# Fuel_Gauge.net
KiCad netlist of a schematic drawn in Altium Designer
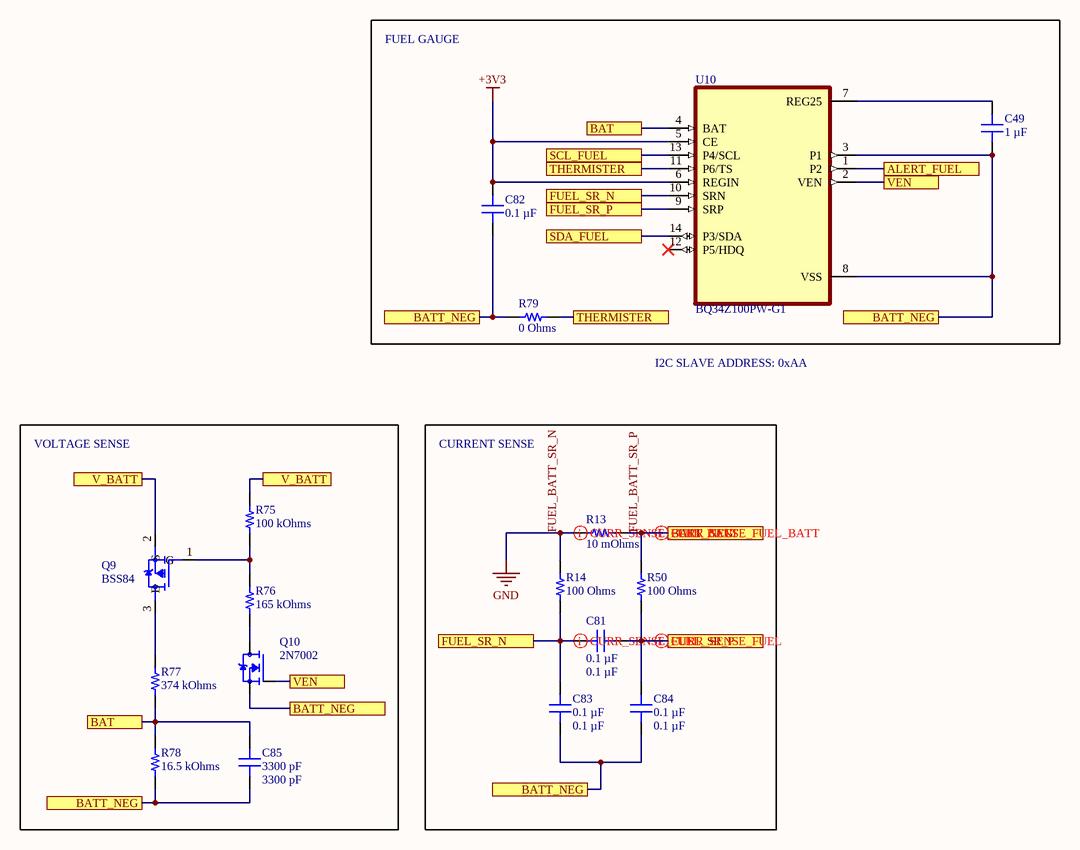
[diagram p0: Fuel_Gauge.SchDoc]

(export (version "E")
  (design (tool "Eeschema 10.0.6"))
  (components
    (comp (ref "C49")
      (value "1 µF")
      (footprint "CAP 0402_1005")
      (description "CAP CER 1UF 10V X5R 0402")
      (fields (field (name "PART NUMBER") "LMK105BJ105KPLF") (field (name "MANUFACTURER") "Taiyo Yuden"))
      (libsource (lib "Celestial Altium Library - altium_library") (part "Capacitor"))
    )
    (comp (ref "C81")
      (value "0.1 µF")
      (footprint "CAP 0603_1608")
      (description "CAP CER 0.1UF 50V X7R 0603")
      (fields
        (field (name "PART NUMBER") "C0603C104K5RAC7411")
        (field (name "ALTIUM_VALUE") "0.1 µF")
        (field (name "MANUFACTURER") "KEMET")
      )
      (libsource (lib "Celestial Altium Library - altium_library") (part "Capacitor"))
    )
    (comp (ref "C82")
      (value "0.1 µF")
      (footprint "CAP 0402_1005")
      (description "CAP CER 0.1UF 10V X5R 0402")
      (fields (field (name "PART NUMBER") "LMK105BJ104MC-F") (field (name "MANUFACTURER") "Taiyo Yuden"))
      (libsource (lib "Celestial Altium Library - altium_library") (part "Capacitor"))
    )
    (comp (ref "C83")
      (value "0.1 µF")
      (footprint "CAP 0603_1608")
      (description "CAP CER 0.1UF 50V X7R 0603")
      (fields
        (field (name "PART NUMBER") "C0603C104K5RAC7411")
        (field (name "ALTIUM_VALUE") "0.1 µF")
        (field (name "MANUFACTURER") "KEMET")
      )
      (libsource (lib "Celestial Altium Library - altium_library") (part "Capacitor"))
    )
    (comp (ref "C84")
      (value "0.1 µF")
      (footprint "CAP 0603_1608")
      (description "CAP CER 0.1UF 50V X7R 0603")
      (fields
        (field (name "PART NUMBER") "C0603C104K5RAC7411")
        (field (name "ALTIUM_VALUE") "0.1 µF")
        (field (name "MANUFACTURER") "KEMET")
      )
      (libsource (lib "Celestial Altium Library - altium_library") (part "Capacitor"))
    )
    (comp (ref "C85")
      (value "3300 pF")
      (footprint "CAP 0402_1005")
      (description "CAP CER 3300PF 16V X7R 0402")
      (fields
        (field (name "PART NUMBER") "AC0402KRX7R7BB332")
        (field (name "ALTIUM_VALUE") "3300 pF")
        (field (name "MANUFACTURER") "Yageo")
      )
      (libsource (lib "Celestial Altium Library - altium_library") (part "Capacitor"))
    )
    (comp (ref "Q9")
      (value "BSS84")
      (footprint "BSS84:SOT95P240X120-3N")
      (description "BSS84 Series 50 V 10 Ohms P-Ch Enhancement Mode Field Effect Transistor SOT-23-3")
      (fields (field (name "MF") "{'manufacturer': u'ON Semiconductor'}"))
      (libsource (lib "*") (part "BSS84"))
    )
    (comp (ref "Q10")
      (value "2N7002")
      (footprint "2N7002:SOT95P240X111-3N")
      (description "N-Channel 60V 280mA (Ta) 350mW (Ta) Surface Mount SOT-23-3 (TO-236)")
      (fields (field (name "MF") "{'manufacturer': u'NTE Electronics, Inc'}"))
      (libsource (lib "*") (part "2N7002"))
    )
    (comp (ref "R13")
      (value "10 mOhms")
      (footprint "RES 1210_3225")
      (description "RES 0.01 OHM 1% 1/2W 1210")
      (fields (field (name "PART NUMBER") "RL1210FR-070R01L") (field (name "MANUFACTURER") "Yageo"))
      (libsource (lib "Celestial Altium Library - altium_library") (part "Resistor"))
    )
    (comp (ref "R14")
      (value "100 Ohms")
      (footprint "RES 0603_1608")
      (description "RES SMD 100 OHM 0.1% 1/10W 0603")
      (fields
        (field (name "PART NUMBER") "ERA-3AEB101V")
        (field (name "MANUFACTURER") "Panasonic Electronic Components")
      )
      (libsource (lib "Celestial Altium Library - altium_library") (part "Resistor"))
    )
    (comp (ref "R50")
      (value "100 Ohms")
      (footprint "RES 0603_1608")
      (description "RES SMD 100 OHM 0.1% 1/10W 0603")
      (fields
        (field (name "PART NUMBER") "ERA-3AEB101V")
        (field (name "MANUFACTURER") "Panasonic Electronic Components")
      )
      (libsource (lib "Celestial Altium Library - altium_library") (part "Resistor"))
    )
    (comp (ref "R75")
      (value "100 kOhms")
      (footprint "RES 0402_1005")
      (description "RES 100K OHM 0.1% 1/10W 0402")
      (fields
        (field (name "PART NUMBER") "RP73PF1E100KBTD")
        (field (name "MANUFACTURER") "TE Connectivity Passive Product")
      )
      (libsource (lib "Celestial Altium Library - altium_library") (part "Resistor"))
    )
    (comp (ref "R76")
      (value "165 kOhms")
      (footprint "RES 0402_1005")
      (description "RES 165K OHM 0.1% 1/10W 0402")
      (fields
        (field (name "PART NUMBER") "RP73PF1E165KBTD")
        (field (name "MANUFACTURER") "TE Connectivity Passive Product")
      )
      (libsource (lib "Celestial Altium Library - altium_library") (part "Resistor"))
    )
    (comp (ref "R77")
      (value "374 kOhms")
      (footprint "RES 0402_1005")
      (description "RES SMD 374K OHM 1% 1/10W 0402")
      (fields
        (field (name "PART NUMBER") "ERJ-2RKF3743X")
        (field (name "MANUFACTURER") "Panasonic Electronic Components")
      )
      (libsource (lib "Celestial Altium Library - altium_library") (part "Resistor"))
    )
    (comp (ref "R78")
      (value "16.5 kOhms")
      (footprint "RES 0603_1608")
      (description "RES SMD 16.5K OHM 0.1% 1/6W 0603")
      (fields
        (field (name "PART NUMBER") "1-2176089-8")
        (field (name "MANUFACTURER") "TE Connectivity Passive Product")
      )
      (libsource (lib "Celestial Altium Library - altium_library") (part "Resistor"))
    )
    (comp (ref "R79")
      (value "0 Ohms")
      (footprint "RES 0805_2012")
      (description "0805 35 AMP JUMPER")
      (fields (field (name "PART NUMBER") "JR0805X35E") (field (name "MANUFACTURER") "Ohmite"))
      (libsource (lib "Celestial Altium Library - altium_library") (part "Resistor"))
    )
    (comp (ref "U10")
      (value "BQ34Z100PW-G1")
      (footprint "BQ34Z100PW-G1:SOP65P640X120-14N")
      (fields (field (name "MF") "{'manufacturer': u'Texas Instruments'}"))
      (libsource (lib "*") (part "BQ34Z100PW-G1"))
    )
  )
  (nets
    (net (code "1") (name "+3V3") (class "Default")
      (node (ref "C82") (pin "2") (pinfunction "2_2") (pintype "passive"))
      (node (ref "U10") (pin "5") (pinfunction "CE_5") (pintype "input"))
      (node (ref "U10") (pin "6") (pinfunction "REGIN_6") (pintype "input"))
    )
    (net (code "2") (name "/ALERT_FUEL") (class "Default")
      (node (ref "U10") (pin "1") (pinfunction "P2_1") (pintype "output"))
    )
    (net (code "3") (name "/BAT") (class "Default")
      (node (ref "C85") (pin "2") (pinfunction "2_2") (pintype "passive"))
      (node (ref "R77") (pin "1") (pinfunction "1_1") (pintype "passive"))
      (node (ref "R78") (pin "2") (pinfunction "2_2") (pintype "passive"))
      (node (ref "U10") (pin "4") (pinfunction "BAT_4") (pintype "input"))
    )
    (net (code "4") (name "/FUEL_BATT_SR_P") (class "Default")
      (node (ref "C49") (pin "1") (pinfunction "1_1") (pintype "passive"))
      (node (ref "C82") (pin "1") (pinfunction "1_1") (pintype "passive"))
      (node (ref "C83") (pin "1") (pinfunction "1_1") (pintype "passive"))
      (node (ref "C84") (pin "1") (pinfunction "1_1") (pintype "passive"))
      (node (ref "C85") (pin "1") (pinfunction "1_1") (pintype "passive"))
      (node (ref "Q10") (pin "2") (pinfunction "S_2") (pintype "passive"))
      (node (ref "R13") (pin "2") (pinfunction "2_2") (pintype "passive"))
      (node (ref "R50") (pin "2") (pinfunction "2_2") (pintype "passive"))
      (node (ref "R78") (pin "1") (pinfunction "1_1") (pintype "passive"))
      (node (ref "R79") (pin "1") (pinfunction "1_1") (pintype "passive"))
      (node (ref "U10") (pin "3") (pinfunction "P1_3") (pintype "output"))
      (node (ref "U10") (pin "8") (pinfunction "VSS_8") (pintype "power_in"))
    )
    (net (code "5") (name "/FUEL_SR_N") (class "Default")
      (node (ref "C81") (pin "2") (pinfunction "2_2") (pintype "passive"))
      (node (ref "C83") (pin "2") (pinfunction "2_2") (pintype "passive"))
      (node (ref "R14") (pin "1") (pinfunction "1_1") (pintype "passive"))
      (node (ref "U10") (pin "10") (pinfunction "SRN_10") (pintype "input"))
    )
    (net (code "6") (name "/FUEL_SR_P") (class "Default")
      (node (ref "C81") (pin "1") (pinfunction "1_1") (pintype "passive"))
      (node (ref "C84") (pin "2") (pinfunction "2_2") (pintype "passive"))
      (node (ref "R50") (pin "1") (pinfunction "1_1") (pintype "passive"))
      (node (ref "U10") (pin "9") (pinfunction "SRP_9") (pintype "input"))
    )
    (net (code "7") (name "/SCL_FUEL") (class "Default")
      (node (ref "U10") (pin "13") (pinfunction "P4/SCL_13") (pintype "input"))
    )
    (net (code "8") (name "/SDA_FUEL") (class "Default")
      (node (ref "U10") (pin "14") (pinfunction "P3/SDA_14") (pintype "bidirectional"))
    )
    (net (code "9") (name "/THERMISTER") (class "Default")
      (node (ref "R79") (pin "2") (pinfunction "2_2") (pintype "passive"))
      (node (ref "U10") (pin "11") (pinfunction "P6/TS_11") (pintype "input"))
    )
    (net (code "10") (name "/VEN") (class "Default")
      (node (ref "Q10") (pin "1") (pinfunction "G_1") (pintype "passive"))
      (node (ref "U10") (pin "2") (pinfunction "VEN_2") (pintype "output"))
    )
    (net (code "11") (name "/V_BATT") (class "Default")
      (node (ref "Q9") (pin "2") (pinfunction "S_2") (pintype "passive"))
      (node (ref "R75") (pin "2") (pinfunction "2_2") (pintype "passive"))
    )
    (net (code "12") (name "GND") (class "Default")
      (node (ref "R13") (pin "1") (pinfunction "1_1") (pintype "passive"))
      (node (ref "R14") (pin "2") (pinfunction "2_2") (pintype "passive"))
    )
    (net (code "13") (name "Net-(Q9-D)") (class "Default")
      (node (ref "Q9") (pin "3") (pinfunction "D_3") (pintype "passive"))
      (node (ref "R77") (pin "2") (pinfunction "2_2") (pintype "passive"))
    )
    (net (code "14") (name "Net-(Q9-G)") (class "Default")
      (node (ref "Q9") (pin "1") (pinfunction "G_1") (pintype "passive"))
      (node (ref "R75") (pin "1") (pinfunction "1_1") (pintype "passive"))
      (node (ref "R76") (pin "2") (pinfunction "2_2") (pintype "passive"))
    )
    (net (code "15") (name "Net-(Q10-D)") (class "Default")
      (node (ref "Q10") (pin "3") (pinfunction "D_3") (pintype "passive"))
      (node (ref "R76") (pin "1") (pinfunction "1_1") (pintype "passive"))
    )
    (net (code "16") (name "Net-(U10-REG25)") (class "Default")
      (node (ref "C49") (pin "2") (pinfunction "2_2") (pintype "passive"))
      (node (ref "U10") (pin "7") (pinfunction "REG25_7") (pintype "power_in"))
    )
    (net (code "17") (name "unconnected-(U10-P5{slash}HDQ-Pad12)") (class "Default")
      (node (ref "U10") (pin "12") (pinfunction "P5/HDQ_12") (pintype "bidirectional+no_connect"))
    )
  )
)
